# 03_-_MODULE_BLE.net
KiCad netlist of a schematic drawn in Altium Designer
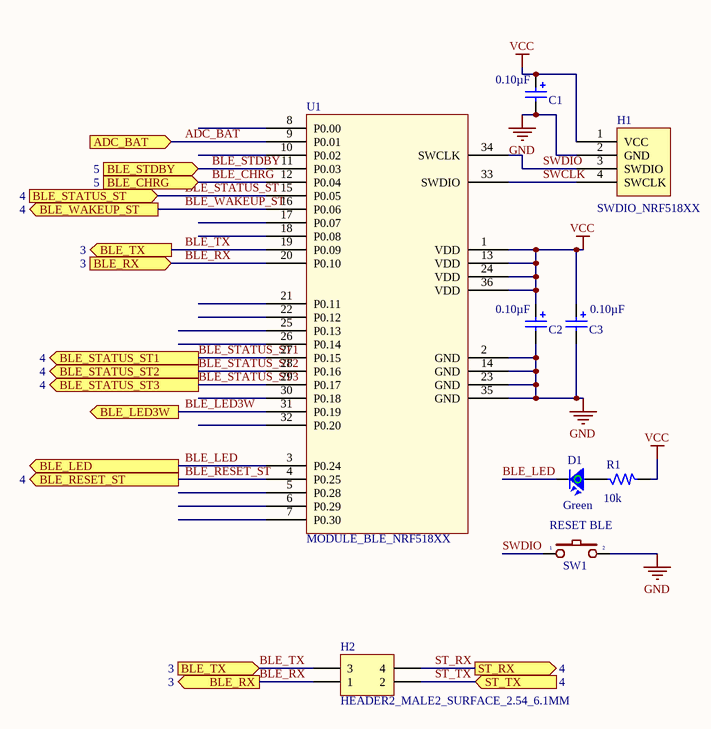
[diagram p0: [03] - MODULE BLE.SchDoc]

(export (version "E")
  (design (tool "Eeschema 10.0.6"))
  (components
    (comp (ref "C1")
      (value "C_104_0603_CERAMIC_16V")
      (footprint "CAP_SMD0603")
      (description "CAP CER 0.1UF 16V X7R 0603")
      (fields
        (field (name "MANUFACTURER") "Murata Electronics North America")
        (field (name "MANUFACTURER PART NUMBER") "GRM188R71C104KA01D")
        (field (name "CAPACITANCE") "0.10µF")
      )
      (libsource (lib "ALTIUM_LIB") (part "C_104_0603_CERAMIC_16V"))
    )
    (comp (ref "C2")
      (value "C_104_0603_CERAMIC_16V")
      (footprint "CAP_SMD0603")
      (description "CAP CER 0.1UF 16V X7R 0603")
      (fields
        (field (name "MANUFACTURER") "Murata Electronics North America")
        (field (name "MANUFACTURER PART NUMBER") "GRM188R71C104KA01D")
        (field (name "CAPACITANCE") "0.10µF")
      )
      (libsource (lib "ALTIUM_LIB") (part "C_104_0603_CERAMIC_16V"))
    )
    (comp (ref "C3")
      (value "C_104_0603_CERAMIC_16V")
      (footprint "CAP_SMD0603")
      (description "CAP CER 0.1UF 16V X7R 0603")
      (fields
        (field (name "MANUFACTURER") "Murata Electronics North America")
        (field (name "MANUFACTURER PART NUMBER") "GRM188R71C104KA01D")
        (field (name "CAPACITANCE") "0.10µF")
      )
      (libsource (lib "ALTIUM_LIB") (part "C_104_0603_CERAMIC_16V"))
    )
    (comp (ref "D1")
      (value "LED2_GREEN_0603_2V")
      (footprint "LED_GREEN_SMD0603")
      (description "LED GREEN CLEAR 0603 SMD")
      (fields
        (field (name "MANUFACTURER") "Lite-On Inc.")
        (field (name "MANUFACTURER PART NUMBER") "LTST-C191KGKT")
        (field (name "COLOR") "Green")
      )
      (libsource (lib "ALTIUM_LIB") (part "LED2_GREEN_0603_2V"))
    )
    (comp (ref "H1")
      (value "SWDIO_NRF518XX")
      (footprint "HEADER4_ISP_NRF518xx_SUR1.27")
      (description "CONN HEADER 4POS .100 STR TIN")
      (fields
        (field (name "MANUFACTURER") "Amphenol FCI")
        (field (name "MANUFACTURER PART NUMBER") "68002-404HLF")
      )
      (libsource (lib "ALTIUM_LIB") (part "HEADER4_ISP_NRF518XX_HOLE_2.54"))
    )
    (comp (ref "H2")
      (value "HEADER2_MALE2_SURFACE_2.54_6.1MM")
      (footprint "HEADER2_MALE2_SUR2.54")
      (description "CONN HEADER 4POS TIN SMD")
      (fields
        (field (name "MANUFACTURER") "Molex, LLC")
        (field (name "MANUFACTURER PART NUMBER") "0015912040")
      )
      (libsource (lib "SchematicLib") (part "HEADER2_MALE2_SURFACE_2.54_6.1MM"))
    )
    (comp (ref "R1")
      (value "R_10K_SMD0603_1%_1/10W")
      (footprint "RES_SMD0603")
      (description "RES SMD 10K OHM 1% 1/10W 0603")
      (fields
        (field (name "MANUFACTURER") "Yageo")
        (field (name "MANUFACTURER PART NUMBER") "RC0603FR-0710KL")
        (field (name "RESISTANCE (OHMS)") "10k")
      )
      (libsource (lib "ALTIUM_LIB") (part "R_10K_SMD0603_1%_1/10W"))
    )
    (comp (ref "SW1")
      (value "RESET BLE")
      (footprint "SW2-SMD")
      (description "SWITCH TACTILE SPST-NO 0.05A 12V")
      (fields
        (field (name "MANUFACTURER") "Wurth Electronics Inc")
        (field (name "MANUFACTURER PART NUMBER") "434121050836")
      )
      (libsource (lib "ALTIUM_LIB") (part "SW2_DPST_SURFACE_5MM"))
    )
    (comp (ref "U1")
      (value "MODULE_BLE_NRF518XX")
      (footprint "MODULE_NRF518xx")
      (libsource (lib "ALTIUM_LIB") (part "MODULE_BLE_NRF518XX"))
    )
  )
  (nets
    (net (code "1") (name "/ADC_BAT") (class "Default")
      (node (ref "U1") (pin "9") (pinfunction "P0.01_9") (pintype "passive"))
    )
    (net (code "2") (name "/BLE_CHRG") (class "Default")
      (node (ref "U1") (pin "12") (pinfunction "P0.04_12") (pintype "passive"))
    )
    (net (code "3") (name "/BLE_LED") (class "Default")
      (node (ref "D1") (pin "2") (pinfunction "2_2") (pintype "passive"))
      (node (ref "U1") (pin "3") (pinfunction "P0.24_3") (pintype "passive"))
    )
    (net (code "4") (name "/BLE_LED3W") (class "Default")
      (node (ref "U1") (pin "31") (pinfunction "P0.19_31") (pintype "passive"))
    )
    (net (code "5") (name "/BLE_RESET_ST") (class "Default")
      (node (ref "U1") (pin "4") (pinfunction "P0.25_4") (pintype "passive"))
    )
    (net (code "6") (name "/BLE_RX") (class "Default")
      (node (ref "H2") (pin "1") (pinfunction "1_1") (pintype "passive"))
      (node (ref "U1") (pin "20") (pinfunction "P0.10_20") (pintype "passive"))
    )
    (net (code "7") (name "/BLE_STATUS_ST") (class "Default")
      (node (ref "U1") (pin "15") (pinfunction "P0.05_15") (pintype "passive"))
    )
    (net (code "8") (name "/BLE_STATUS_ST1") (class "Default")
      (node (ref "U1") (pin "27") (pinfunction "P0.15_27") (pintype "passive"))
    )
    (net (code "9") (name "/BLE_STATUS_ST2") (class "Default")
      (node (ref "U1") (pin "28") (pinfunction "P0.16_28") (pintype "passive"))
    )
    (net (code "10") (name "/BLE_STATUS_ST3") (class "Default")
      (node (ref "U1") (pin "29") (pinfunction "P0.17_29") (pintype "passive"))
    )
    (net (code "11") (name "/BLE_STDBY") (class "Default")
      (node (ref "U1") (pin "11") (pinfunction "P0.03_11") (pintype "passive"))
    )
    (net (code "12") (name "/BLE_TX") (class "Default")
      (node (ref "H2") (pin "3") (pinfunction "3_3") (pintype "passive"))
      (node (ref "U1") (pin "19") (pinfunction "P0.09_19") (pintype "passive"))
    )
    (net (code "13") (name "/BLE_WAKEUP_ST") (class "Default")
      (node (ref "U1") (pin "16") (pinfunction "P0.06_16") (pintype "passive"))
    )
    (net (code "14") (name "/ST_RX") (class "Default")
      (node (ref "H2") (pin "4") (pinfunction "4_4") (pintype "passive"))
    )
    (net (code "15") (name "/ST_TX") (class "Default")
      (node (ref "H2") (pin "2") (pinfunction "2_2") (pintype "passive"))
    )
    (net (code "16") (name "/SWCLK") (class "Default")
      (node (ref "H1") (pin "4") (pinfunction "SWCLK_4") (pintype "passive"))
      (node (ref "U1") (pin "33") (pinfunction "SWDIO_33") (pintype "passive"))
    )
    (net (code "17") (name "/SWDIO") (class "Default")
      (node (ref "H1") (pin "3") (pinfunction "SWDIO_3") (pintype "passive"))
      (node (ref "SW1") (pin "1") (pinfunction "1_1") (pintype "passive"))
      (node (ref "U1") (pin "34") (pinfunction "SWCLK_34") (pintype "passive"))
    )
    (net (code "18") (name "GND") (class "Default")
      (node (ref "C1") (pin "2") (pinfunction "2_2") (pintype "passive"))
      (node (ref "C2") (pin "2") (pinfunction "2_2") (pintype "passive"))
      (node (ref "C3") (pin "2") (pinfunction "2_2") (pintype "passive"))
      (node (ref "H1") (pin "2") (pinfunction "GND_2") (pintype "passive"))
      (node (ref "SW1") (pin "2") (pinfunction "2_2") (pintype "passive"))
      (node (ref "U1") (pin "14") (pinfunction "GND_14") (pintype "passive"))
      (node (ref "U1") (pin "2") (pinfunction "GND_2") (pintype "passive"))
      (node (ref "U1") (pin "23") (pinfunction "GND_23") (pintype "passive"))
      (node (ref "U1") (pin "35") (pinfunction "GND_35") (pintype "passive"))
    )
    (net (code "19") (name "Net-(D1-Pad1)") (class "Default")
      (node (ref "D1") (pin "1") (pinfunction "1_1") (pintype "passive"))
      (node (ref "R1") (pin "1") (pinfunction "1_1") (pintype "passive"))
    )
    (net (code "20") (name "VCC") (class "Default")
      (node (ref "C1") (pin "1") (pinfunction "1_1") (pintype "passive"))
      (node (ref "C2") (pin "1") (pinfunction "1_1") (pintype "passive"))
      (node (ref "C3") (pin "1") (pinfunction "1_1") (pintype "passive"))
      (node (ref "H1") (pin "1") (pinfunction "VCC_1") (pintype "passive"))
      (node (ref "R1") (pin "2") (pinfunction "2_2") (pintype "passive"))
      (node (ref "U1") (pin "1") (pinfunction "VDD_1") (pintype "passive"))
      (node (ref "U1") (pin "13") (pinfunction "VDD_13") (pintype "passive"))
      (node (ref "U1") (pin "24") (pinfunction "VDD_24") (pintype "passive"))
      (node (ref "U1") (pin "36") (pinfunction "VDD_36") (pintype "passive"))
    )
    (net (code "21") (name "unconnected-(U1-P0.00-Pad8)") (class "Default")
      (node (ref "U1") (pin "8") (pinfunction "P0.00_8") (pintype "passive"))
    )
    (net (code "22") (name "unconnected-(U1-P0.02-Pad10)") (class "Default")
      (node (ref "U1") (pin "10") (pinfunction "P0.02_10") (pintype "passive"))
    )
    (net (code "23") (name "unconnected-(U1-P0.07-Pad17)") (class "Default")
      (node (ref "U1") (pin "17") (pinfunction "P0.07_17") (pintype "passive"))
    )
    (net (code "24") (name "unconnected-(U1-P0.08-Pad18)") (class "Default")
      (node (ref "U1") (pin "18") (pinfunction "P0.08_18") (pintype "passive"))
    )
    (net (code "25") (name "unconnected-(U1-P0.11-Pad21)") (class "Default")
      (node (ref "U1") (pin "21") (pinfunction "P0.11_21") (pintype "passive"))
    )
    (net (code "26") (name "unconnected-(U1-P0.12-Pad22)") (class "Default")
      (node (ref "U1") (pin "22") (pinfunction "P0.12_22") (pintype "passive"))
    )
    (net (code "27") (name "unconnected-(U1-P0.13-Pad25)") (class "Default")
      (node (ref "U1") (pin "25") (pinfunction "P0.13_25") (pintype "passive"))
    )
    (net (code "28") (name "unconnected-(U1-P0.14-Pad26)") (class "Default")
      (node (ref "U1") (pin "26") (pinfunction "P0.14_26") (pintype "passive"))
    )
    (net (code "29") (name "unconnected-(U1-P0.18-Pad30)") (class "Default")
      (node (ref "U1") (pin "30") (pinfunction "P0.18_30") (pintype "passive"))
    )
    (net (code "30") (name "unconnected-(U1-P0.20-Pad32)") (class "Default")
      (node (ref "U1") (pin "32") (pinfunction "P0.20_32") (pintype "passive"))
    )
    (net (code "31") (name "unconnected-(U1-P0.28-Pad5)") (class "Default")
      (node (ref "U1") (pin "5") (pinfunction "P0.28_5") (pintype "passive"))
    )
    (net (code "32") (name "unconnected-(U1-P0.29-Pad6)") (class "Default")
      (node (ref "U1") (pin "6") (pinfunction "P0.29_6") (pintype "passive"))
    )
    (net (code "33") (name "unconnected-(U1-P0.30-Pad7)") (class "Default")
      (node (ref "U1") (pin "7") (pinfunction "P0.30_7") (pintype "passive"))
    )
  )
)
